# DHT22.net
KiCad netlist of a schematic drawn in EAGLE
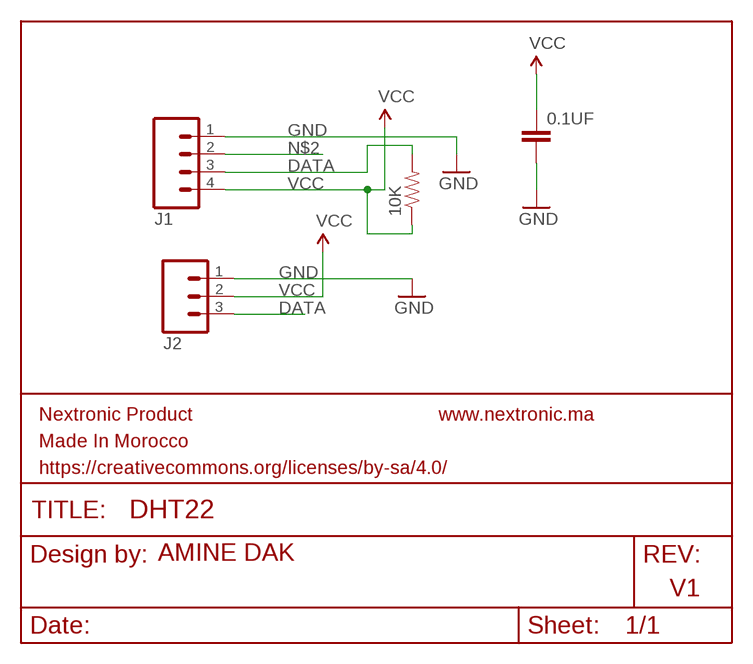
[diagram p0: schematic, sheet 1]

(export (version "E")
  (design (tool "Eeschema 10.0.6"))
  (components
    (comp (ref "0.1UF")
      (value "CAP0603-CAP")
      (footprint "eagle-import:0603-CAP")
      (libsource (lib "eagle-import") (part "CAP0603-CAP"))
    )
    (comp (ref "10K")
      (value "RESISTOR0603-RES")
      (footprint "eagle-import:0603-RES")
      (libsource (lib "eagle-import") (part "RESISTOR0603-RES"))
    )
    (comp (ref "J1")
      (value "M04PTH")
      (footprint "eagle-import:1X04")
      (libsource (lib "eagle-import") (part "M04PTH"))
    )
    (comp (ref "J2")
      (value "M03PTH")
      (footprint "eagle-import:1X03")
      (libsource (lib "eagle-import") (part "M03PTH"))
    )
  )
  (nets
    (net (code "1") (name "/DATA") (class "Default")
      (node (ref "10K") (pin "2") (pinfunction "2_2") (pintype "passive"))
      (node (ref "J1") (pin "3") (pinfunction "3_3") (pintype "passive"))
      (node (ref "J2") (pin "3") (pinfunction "3_3") (pintype "passive"))
    )
    (net (code "2") (name "/N$2") (class "Default")
      (node (ref "J1") (pin "2") (pinfunction "2_2") (pintype "passive"))
    )
    (net (code "3") (name "GND") (class "Default")
      (node (ref "0.1UF") (pin "2") (pinfunction "2_2") (pintype "passive"))
      (node (ref "J1") (pin "1") (pinfunction "1_1") (pintype "passive"))
      (node (ref "J2") (pin "1") (pinfunction "1_1") (pintype "passive"))
    )
    (net (code "4") (name "VCC") (class "Default")
      (node (ref "0.1UF") (pin "1") (pinfunction "1_1") (pintype "passive"))
      (node (ref "10K") (pin "1") (pinfunction "1_1") (pintype "passive"))
      (node (ref "J1") (pin "4") (pinfunction "4_4") (pintype "passive"))
      (node (ref "J2") (pin "2") (pinfunction "2_2") (pintype "passive"))
    )
  )
)
